# lm3410-boost-50ma.net
KiCad netlist of a schematic drawn in EAGLE
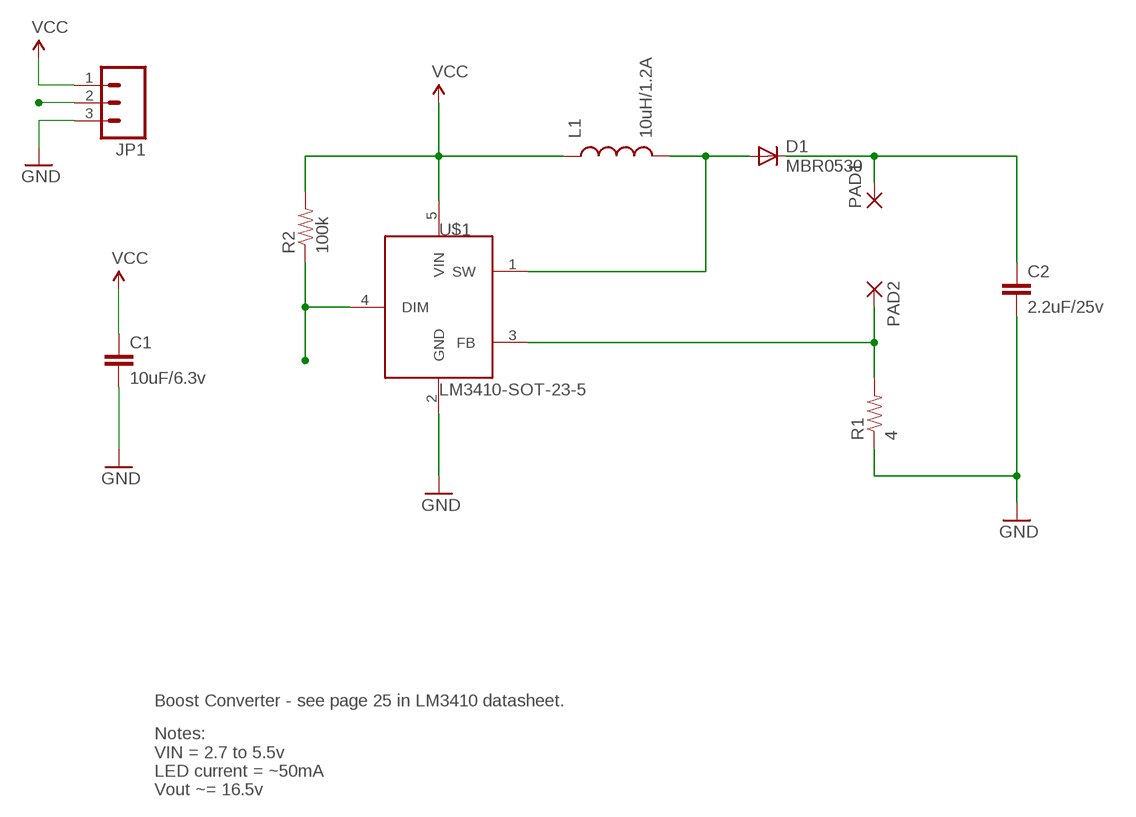
[diagram p0: schematic, sheet 1]

(export (version "E")
  (design (tool "Eeschema 10.0.6"))
  (components
    (comp (ref "C1")
      (value "10uF/6.3v")
      (footprint "eagle-import:1206")
      (libsource (lib "eagle-import") (part "CAP1206"))
    )
    (comp (ref "C2")
      (value "2.2uF/25v")
      (footprint "eagle-import:1206")
      (libsource (lib "eagle-import") (part "SparkFun-Passives_CAP1206"))
    )
    (comp (ref "D1")
      (value "MBR0530")
      (footprint "eagle-import:SOD123")
      (libsource (lib "eagle-import") (part "MBR0520LT"))
    )
    (comp (ref "JP1")
      (value "M03PTH")
      (footprint "eagle-import:1X03")
      (libsource (lib "eagle-import") (part "M03PTH"))
    )
    (comp (ref "L1")
      (value "10uH/1.2A")
      (footprint "eagle-import:1210")
      (libsource (lib "eagle-import") (part "INDUCTOR1210"))
    )
    (comp (ref "PAD1")
      (value "2,54/1,0")
      (footprint "eagle-import:2,54_1,0")
      (libsource (lib "eagle-import") (part "2,54/1,0"))
    )
    (comp (ref "PAD2")
      (value "2,54/1,0")
      (footprint "eagle-import:2,54_1,0")
      (libsource (lib "eagle-import") (part "2,54/1,0"))
    )
    (comp (ref "R1")
      (value "4")
      (footprint "eagle-import:1206")
      (libsource (lib "eagle-import") (part "RESISTOR1206"))
    )
    (comp (ref "R2")
      (value "100k")
      (footprint "eagle-import:0603-RES")
      (libsource (lib "eagle-import") (part "RESISTOR0603-RES"))
    )
    (comp (ref "U$1")
      (value "LM3410-SOT-23-5")
      (footprint "eagle-import:SOT-23-5")
      (libsource (lib "eagle-import") (part "LM3410-SOT-23-5"))
    )
  )
  (nets
    (net (code "1") (name "/DIM") (class "Default")
      (node (ref "JP1") (pin "2") (pinfunction "2_2") (pintype "passive"))
      (node (ref "R2") (pin "1") (pinfunction "1_1") (pintype "passive"))
      (node (ref "U$1") (pin "4") (pinfunction "DIM_4") (pintype "bidirectional"))
    )
    (net (code "2") (name "GND") (class "Default")
      (node (ref "C1") (pin "2") (pinfunction "2_2") (pintype "passive"))
      (node (ref "C2") (pin "2") (pinfunction "2_2") (pintype "passive"))
      (node (ref "JP1") (pin "3") (pinfunction "3_3") (pintype "passive"))
      (node (ref "R1") (pin "1") (pinfunction "1_1") (pintype "passive"))
      (node (ref "U$1") (pin "2") (pinfunction "GND_2") (pintype "bidirectional"))
    )
    (net (code "3") (name "Net-(PAD1-P)") (class "Default")
      (node (ref "C2") (pin "1") (pinfunction "1_1") (pintype "passive"))
      (node (ref "D1") (pin "C") (pinfunction "C_C") (pintype "passive"))
      (node (ref "PAD1") (pin "1") (pinfunction "P_1") (pintype "passive"))
    )
    (net (code "4") (name "Net-(PAD2-P)") (class "Default")
      (node (ref "PAD2") (pin "1") (pinfunction "P_1") (pintype "passive"))
      (node (ref "R1") (pin "2") (pinfunction "2_2") (pintype "passive"))
      (node (ref "U$1") (pin "3") (pinfunction "FB_3") (pintype "bidirectional"))
    )
    (net (code "5") (name "Net-(U$1-SW)") (class "Default")
      (node (ref "D1") (pin "A") (pinfunction "A_A") (pintype "passive"))
      (node (ref "L1") (pin "2") (pinfunction "2_2") (pintype "passive"))
      (node (ref "U$1") (pin "1") (pinfunction "SW_1") (pintype "bidirectional"))
    )
    (net (code "6") (name "VCC") (class "Default")
      (node (ref "C1") (pin "1") (pinfunction "1_1") (pintype "passive"))
      (node (ref "JP1") (pin "1") (pinfunction "1_1") (pintype "passive"))
      (node (ref "L1") (pin "1") (pinfunction "1_1") (pintype "passive"))
      (node (ref "R2") (pin "2") (pinfunction "2_2") (pintype "passive"))
      (node (ref "U$1") (pin "5") (pinfunction "VIN_5") (pintype "bidirectional"))
    )
  )
)
